# Optimus_Prime.net
KiCad netlist of a schematic drawn in EasyEDA Pro
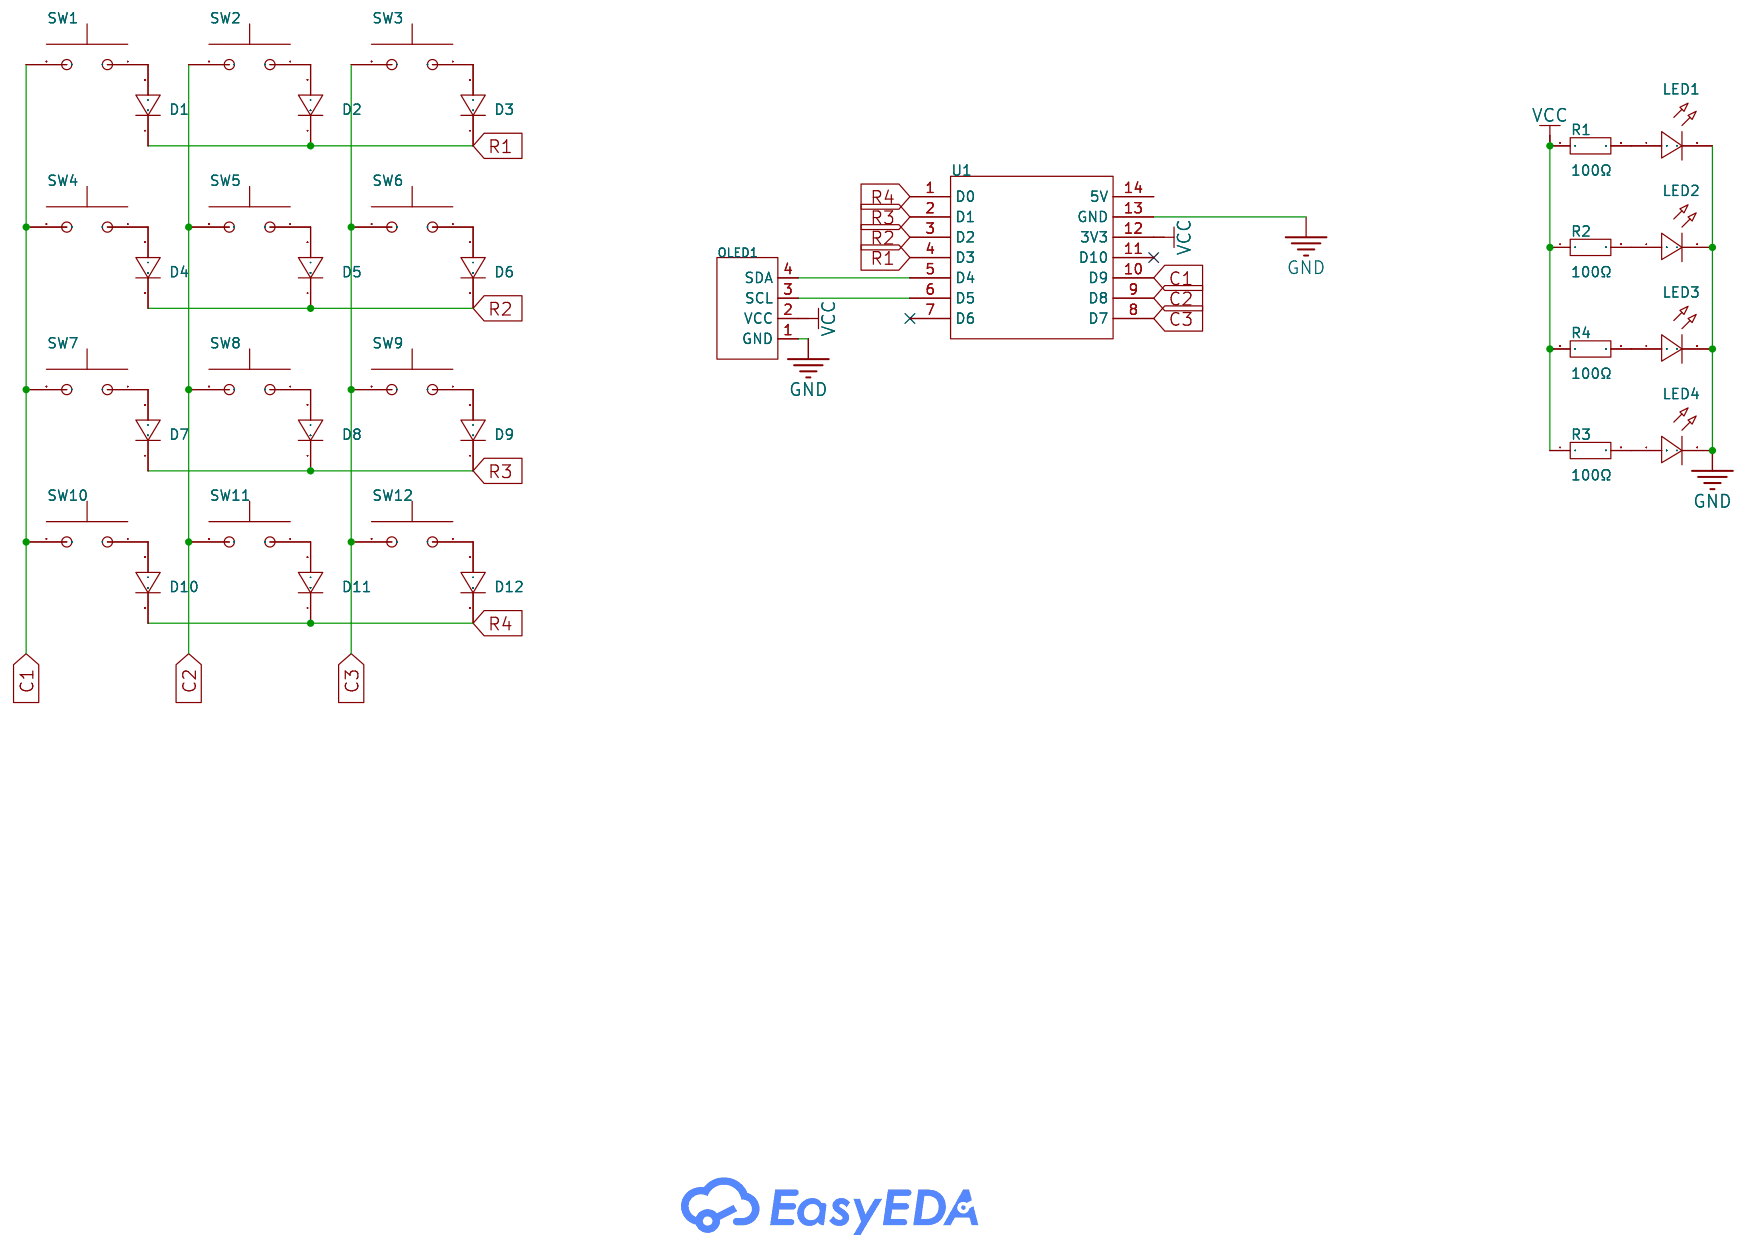
[diagram p0: schematic sheet]

(export (version "E")
  (design (tool "Eeschema 10.0.6"))
  (components
    (comp (ref "D1")
      (value "1N4148TR")
      (footprint "easyedapro:DO-35_BD2.0-L4.2-P8.20-D0.5-RD")
      (fields (field (name "Manufacturer") "VISHAY(威世)"))
      (libsource (lib "easyedapro") (part "1N4148TR-C84412"))
    )
    (comp (ref "D2")
      (value "1N4148TR")
      (footprint "easyedapro:DO-35_BD2.0-L4.2-P8.20-D0.5-RD")
      (fields (field (name "Manufacturer") "VISHAY(威世)"))
      (libsource (lib "easyedapro") (part "1N4148TR-C84412"))
    )
    (comp (ref "D3")
      (value "1N4148TR")
      (footprint "easyedapro:DO-35_BD2.0-L4.2-P8.20-D0.5-RD")
      (fields (field (name "Manufacturer") "VISHAY(威世)"))
      (libsource (lib "easyedapro") (part "1N4148TR-C84412"))
    )
    (comp (ref "D4")
      (value "1N4148TR")
      (footprint "easyedapro:DO-35_BD2.0-L4.2-P8.20-D0.5-RD")
      (fields (field (name "Manufacturer") "VISHAY(威世)"))
      (libsource (lib "easyedapro") (part "1N4148TR-C84412"))
    )
    (comp (ref "D5")
      (value "1N4148TR")
      (footprint "easyedapro:DO-35_BD2.0-L4.2-P8.20-D0.5-RD")
      (fields (field (name "Manufacturer") "VISHAY(威世)"))
      (libsource (lib "easyedapro") (part "1N4148TR-C84412"))
    )
    (comp (ref "D6")
      (value "1N4148TR")
      (footprint "easyedapro:DO-35_BD2.0-L4.2-P8.20-D0.5-RD")
      (fields (field (name "Manufacturer") "VISHAY(威世)"))
      (libsource (lib "easyedapro") (part "1N4148TR-C84412"))
    )
    (comp (ref "D7")
      (value "1N4148TR")
      (footprint "easyedapro:DO-35_BD2.0-L4.2-P8.20-D0.5-RD")
      (fields (field (name "Manufacturer") "VISHAY(威世)"))
      (libsource (lib "easyedapro") (part "1N4148TR-C84412"))
    )
    (comp (ref "D8")
      (value "1N4148TR")
      (footprint "easyedapro:DO-35_BD2.0-L4.2-P8.20-D0.5-RD")
      (fields (field (name "Manufacturer") "VISHAY(威世)"))
      (libsource (lib "easyedapro") (part "1N4148TR-C84412"))
    )
    (comp (ref "D9")
      (value "1N4148TR")
      (footprint "easyedapro:DO-35_BD2.0-L4.2-P8.20-D0.5-RD")
      (fields (field (name "Manufacturer") "VISHAY(威世)"))
      (libsource (lib "easyedapro") (part "1N4148TR-C84412"))
    )
    (comp (ref "D10")
      (value "1N4148TR")
      (footprint "easyedapro:DO-35_BD2.0-L4.2-P8.20-D0.5-RD")
      (fields (field (name "Manufacturer") "VISHAY(威世)"))
      (libsource (lib "easyedapro") (part "1N4148TR-C84412"))
    )
    (comp (ref "D11")
      (value "1N4148TR")
      (footprint "easyedapro:DO-35_BD2.0-L4.2-P8.20-D0.5-RD")
      (fields (field (name "Manufacturer") "VISHAY(威世)"))
      (libsource (lib "easyedapro") (part "1N4148TR-C84412"))
    )
    (comp (ref "D12")
      (value "1N4148TR")
      (footprint "easyedapro:DO-35_BD2.0-L4.2-P8.20-D0.5-RD")
      (fields (field (name "Manufacturer") "VISHAY(威世)"))
      (libsource (lib "easyedapro") (part "1N4148TR-C84412"))
    )
    (comp (ref "LED1")
      (value "~")
      (footprint "easyedapro:LED-TH_BD3.0-P2.54-FD")
      (libsource (lib "easyedapro") (part "LED_TH-R"))
    )
    (comp (ref "LED2")
      (value "~")
      (footprint "easyedapro:LED-TH_BD3.0-P2.54-FD")
      (libsource (lib "easyedapro") (part "LED_TH-R"))
    )
    (comp (ref "LED3")
      (value "~")
      (footprint "easyedapro:LED-TH_BD3.0-P2.54-FD")
      (libsource (lib "easyedapro") (part "LED_TH-R"))
    )
    (comp (ref "LED4")
      (value "~")
      (footprint "easyedapro:LED-TH_BD3.0-P2.54-FD")
      (libsource (lib "easyedapro") (part "LED_TH-R"))
    )
    (comp (ref "OLED1")
      (value "HS91L02W2C01")
      (footprint "easyedapro:OLED-TH_L38.0-W12.0_HS91L02W2C01")
      (fields (field (name "Manufacturer") "HS(汉昇)"))
      (libsource (lib "easyedapro") (part "HS91L02W2C01"))
    )
    (comp (ref "R1")
      (value "100Ω")
      (footprint "easyedapro:RES-TH_BD1.8-L3.2-P7.20-D0.4")
      (libsource (lib "easyedapro") (part "Res"))
    )
    (comp (ref "R2")
      (value "100Ω")
      (footprint "easyedapro:RES-TH_BD1.8-L3.2-P7.20-D0.4")
      (libsource (lib "easyedapro") (part "Res"))
    )
    (comp (ref "R3")
      (value "100Ω")
      (footprint "easyedapro:RES-TH_BD1.8-L3.2-P7.20-D0.4")
      (libsource (lib "easyedapro") (part "Res"))
    )
    (comp (ref "R4")
      (value "100Ω")
      (footprint "easyedapro:RES-TH_BD1.8-L3.2-P7.20-D0.4")
      (libsource (lib "easyedapro") (part "Res"))
    )
    (comp (ref "SW1")
      (value "~")
      (footprint "easyedapro:MX_PCB_1.00u")
      (libsource (lib "easyedapro") (part "MX_1.00U"))
    )
    (comp (ref "SW2")
      (value "~")
      (footprint "easyedapro:MX_PCB_1.00u")
      (libsource (lib "easyedapro") (part "MX_1.00U"))
    )
    (comp (ref "SW3")
      (value "~")
      (footprint "easyedapro:MX_PCB_1.00u")
      (libsource (lib "easyedapro") (part "MX_1.00U"))
    )
    (comp (ref "SW4")
      (value "~")
      (footprint "easyedapro:MX_PCB_1.00u")
      (libsource (lib "easyedapro") (part "MX_1.00U"))
    )
    (comp (ref "SW5")
      (value "~")
      (footprint "easyedapro:MX_PCB_1.00u")
      (libsource (lib "easyedapro") (part "MX_1.00U"))
    )
    (comp (ref "SW6")
      (value "~")
      (footprint "easyedapro:MX_PCB_1.00u")
      (libsource (lib "easyedapro") (part "MX_1.00U"))
    )
    (comp (ref "SW7")
      (value "~")
      (footprint "easyedapro:MX_PCB_1.00u")
      (libsource (lib "easyedapro") (part "MX_1.00U"))
    )
    (comp (ref "SW8")
      (value "~")
      (footprint "easyedapro:MX_PCB_1.00u")
      (libsource (lib "easyedapro") (part "MX_1.00U"))
    )
    (comp (ref "SW9")
      (value "~")
      (footprint "easyedapro:MX_PCB_1.00u")
      (libsource (lib "easyedapro") (part "MX_1.00U"))
    )
    (comp (ref "SW10")
      (value "~")
      (footprint "easyedapro:MX_PCB_1.00u")
      (libsource (lib "easyedapro") (part "MX_1.00U"))
    )
    (comp (ref "SW11")
      (value "~")
      (footprint "easyedapro:MX_PCB_1.00u")
      (libsource (lib "easyedapro") (part "MX_1.00U"))
    )
    (comp (ref "SW12")
      (value "~")
      (footprint "easyedapro:MX_PCB_1.00u")
      (libsource (lib "easyedapro") (part "MX_1.00U"))
    )
    (comp (ref "U1")
      (value "~")
      (footprint "easyedapro:Seeed_XIAO_RP2040")
      (libsource (lib "easyedapro") (part "MCU_XIAO_RP2040"))
    )
  )
  (nets
    (net (code "1") (name "C1") (class "Default")
      (node (ref "SW1") (pin "2") (pinfunction "2_2") (pintype "input"))
      (node (ref "SW10") (pin "2") (pinfunction "2_2") (pintype "input"))
      (node (ref "SW4") (pin "2") (pinfunction "2_2") (pintype "input"))
      (node (ref "SW7") (pin "2") (pinfunction "2_2") (pintype "input"))
      (node (ref "U1") (pin "10") (pinfunction "D9_10") (pintype "input"))
    )
    (net (code "2") (name "C2") (class "Default")
      (node (ref "SW11") (pin "2") (pinfunction "2_2") (pintype "input"))
      (node (ref "SW2") (pin "2") (pinfunction "2_2") (pintype "input"))
      (node (ref "SW5") (pin "2") (pinfunction "2_2") (pintype "input"))
      (node (ref "SW8") (pin "2") (pinfunction "2_2") (pintype "input"))
      (node (ref "U1") (pin "9") (pinfunction "D8_9") (pintype "input"))
    )
    (net (code "3") (name "C3") (class "Default")
      (node (ref "SW12") (pin "2") (pinfunction "2_2") (pintype "input"))
      (node (ref "SW3") (pin "2") (pinfunction "2_2") (pintype "input"))
      (node (ref "SW6") (pin "2") (pinfunction "2_2") (pintype "input"))
      (node (ref "SW9") (pin "2") (pinfunction "2_2") (pintype "input"))
      (node (ref "U1") (pin "8") (pinfunction "D7_8") (pintype "input"))
    )
    (net (code "4") (name "GND") (class "Default")
      (node (ref "LED1") (pin "2") (pinfunction "A_2") (pintype "input"))
      (node (ref "LED2") (pin "2") (pinfunction "A_2") (pintype "input"))
      (node (ref "LED3") (pin "2") (pinfunction "A_2") (pintype "input"))
      (node (ref "LED4") (pin "2") (pinfunction "A_2") (pintype "input"))
      (node (ref "OLED1") (pin "1") (pinfunction "GND_1") (pintype "input"))
      (node (ref "U1") (pin "13") (pinfunction "GND_13") (pintype "input"))
    )
    (net (code "5") (name "Net-(D1-A)") (class "Default")
      (node (ref "D1") (pin "2") (pinfunction "A_2") (pintype "unspecified"))
      (node (ref "SW1") (pin "1") (pinfunction "1_1") (pintype "input"))
    )
    (net (code "6") (name "Net-(D2-A)") (class "Default")
      (node (ref "D2") (pin "2") (pinfunction "A_2") (pintype "unspecified"))
      (node (ref "SW2") (pin "1") (pinfunction "1_1") (pintype "input"))
    )
    (net (code "7") (name "Net-(D3-A)") (class "Default")
      (node (ref "D3") (pin "2") (pinfunction "A_2") (pintype "unspecified"))
      (node (ref "SW3") (pin "1") (pinfunction "1_1") (pintype "input"))
    )
    (net (code "8") (name "Net-(D4-A)") (class "Default")
      (node (ref "D4") (pin "2") (pinfunction "A_2") (pintype "unspecified"))
      (node (ref "SW4") (pin "1") (pinfunction "1_1") (pintype "input"))
    )
    (net (code "9") (name "Net-(D5-A)") (class "Default")
      (node (ref "D5") (pin "2") (pinfunction "A_2") (pintype "unspecified"))
      (node (ref "SW5") (pin "1") (pinfunction "1_1") (pintype "input"))
    )
    (net (code "10") (name "Net-(D6-A)") (class "Default")
      (node (ref "D6") (pin "2") (pinfunction "A_2") (pintype "unspecified"))
      (node (ref "SW6") (pin "1") (pinfunction "1_1") (pintype "input"))
    )
    (net (code "11") (name "Net-(D7-A)") (class "Default")
      (node (ref "D7") (pin "2") (pinfunction "A_2") (pintype "unspecified"))
      (node (ref "SW7") (pin "1") (pinfunction "1_1") (pintype "input"))
    )
    (net (code "12") (name "Net-(D8-A)") (class "Default")
      (node (ref "D8") (pin "2") (pinfunction "A_2") (pintype "unspecified"))
      (node (ref "SW8") (pin "1") (pinfunction "1_1") (pintype "input"))
    )
    (net (code "13") (name "Net-(D9-A)") (class "Default")
      (node (ref "D9") (pin "2") (pinfunction "A_2") (pintype "unspecified"))
      (node (ref "SW9") (pin "1") (pinfunction "1_1") (pintype "input"))
    )
    (net (code "14") (name "Net-(D10-A)") (class "Default")
      (node (ref "D10") (pin "2") (pinfunction "A_2") (pintype "unspecified"))
      (node (ref "SW10") (pin "1") (pinfunction "1_1") (pintype "input"))
    )
    (net (code "15") (name "Net-(D11-A)") (class "Default")
      (node (ref "D11") (pin "2") (pinfunction "A_2") (pintype "unspecified"))
      (node (ref "SW11") (pin "1") (pinfunction "1_1") (pintype "input"))
    )
    (net (code "16") (name "Net-(D12-A)") (class "Default")
      (node (ref "D12") (pin "2") (pinfunction "A_2") (pintype "unspecified"))
      (node (ref "SW12") (pin "1") (pinfunction "1_1") (pintype "input"))
    )
    (net (code "17") (name "Net-(LED1-C)") (class "Default")
      (node (ref "LED1") (pin "1") (pinfunction "C_1") (pintype "input"))
      (node (ref "R1") (pin "2") (pinfunction "2_2") (pintype "input"))
    )
    (net (code "18") (name "Net-(LED2-C)") (class "Default")
      (node (ref "LED2") (pin "1") (pinfunction "C_1") (pintype "input"))
      (node (ref "R2") (pin "2") (pinfunction "2_2") (pintype "input"))
    )
    (net (code "19") (name "Net-(LED3-C)") (class "Default")
      (node (ref "LED3") (pin "1") (pinfunction "C_1") (pintype "input"))
      (node (ref "R4") (pin "2") (pinfunction "2_2") (pintype "input"))
    )
    (net (code "20") (name "Net-(LED4-C)") (class "Default")
      (node (ref "LED4") (pin "1") (pinfunction "C_1") (pintype "input"))
      (node (ref "R3") (pin "2") (pinfunction "2_2") (pintype "input"))
    )
    (net (code "21") (name "Net-(OLED1-SCL)") (class "Default")
      (node (ref "OLED1") (pin "3") (pinfunction "SCL_3") (pintype "input"))
      (node (ref "U1") (pin "6") (pinfunction "D5_6") (pintype "input"))
    )
    (net (code "22") (name "Net-(OLED1-SDA)") (class "Default")
      (node (ref "OLED1") (pin "4") (pinfunction "SDA_4") (pintype "input"))
      (node (ref "U1") (pin "5") (pinfunction "D4_5") (pintype "input"))
    )
    (net (code "23") (name "R1") (class "Default")
      (node (ref "D1") (pin "1") (pinfunction "C_1") (pintype "unspecified"))
      (node (ref "D2") (pin "1") (pinfunction "C_1") (pintype "unspecified"))
      (node (ref "D3") (pin "1") (pinfunction "C_1") (pintype "unspecified"))
      (node (ref "U1") (pin "4") (pinfunction "D3_4") (pintype "input"))
    )
    (net (code "24") (name "R2") (class "Default")
      (node (ref "D4") (pin "1") (pinfunction "C_1") (pintype "unspecified"))
      (node (ref "D5") (pin "1") (pinfunction "C_1") (pintype "unspecified"))
      (node (ref "D6") (pin "1") (pinfunction "C_1") (pintype "unspecified"))
      (node (ref "U1") (pin "3") (pinfunction "D2_3") (pintype "input"))
    )
    (net (code "25") (name "R3") (class "Default")
      (node (ref "D7") (pin "1") (pinfunction "C_1") (pintype "unspecified"))
      (node (ref "D8") (pin "1") (pinfunction "C_1") (pintype "unspecified"))
      (node (ref "D9") (pin "1") (pinfunction "C_1") (pintype "unspecified"))
      (node (ref "U1") (pin "2") (pinfunction "D1_2") (pintype "input"))
    )
    (net (code "26") (name "R4") (class "Default")
      (node (ref "D10") (pin "1") (pinfunction "C_1") (pintype "unspecified"))
      (node (ref "D11") (pin "1") (pinfunction "C_1") (pintype "unspecified"))
      (node (ref "D12") (pin "1") (pinfunction "C_1") (pintype "unspecified"))
      (node (ref "U1") (pin "1") (pinfunction "D0_1") (pintype "input"))
    )
    (net (code "27") (name "VCC") (class "Default")
      (node (ref "OLED1") (pin "2") (pinfunction "VCC_2") (pintype "input"))
      (node (ref "R1") (pin "1") (pinfunction "1_1") (pintype "input"))
      (node (ref "R2") (pin "1") (pinfunction "1_1") (pintype "input"))
      (node (ref "R3") (pin "1") (pinfunction "1_1") (pintype "input"))
      (node (ref "R4") (pin "1") (pinfunction "1_1") (pintype "input"))
      (node (ref "U1") (pin "12") (pinfunction "3V3_12") (pintype "input"))
    )
    (net (code "28") (name "unconnected-(U1-5V-Pad14)") (class "Default")
      (node (ref "U1") (pin "14") (pinfunction "5V_14") (pintype "input"))
    )
    (net (code "29") (name "unconnected-(U1-D6-Pad7)") (class "Default")
      (node (ref "U1") (pin "7") (pinfunction "D6_7") (pintype "input+no_connect"))
    )
    (net (code "30") (name "unconnected-(U1-D10-Pad11)") (class "Default")
      (node (ref "U1") (pin "11") (pinfunction "D10_11") (pintype "input+no_connect"))
    )
  )
)
